# Schematic.net
KiCad netlist of a schematic drawn in Altium Designer
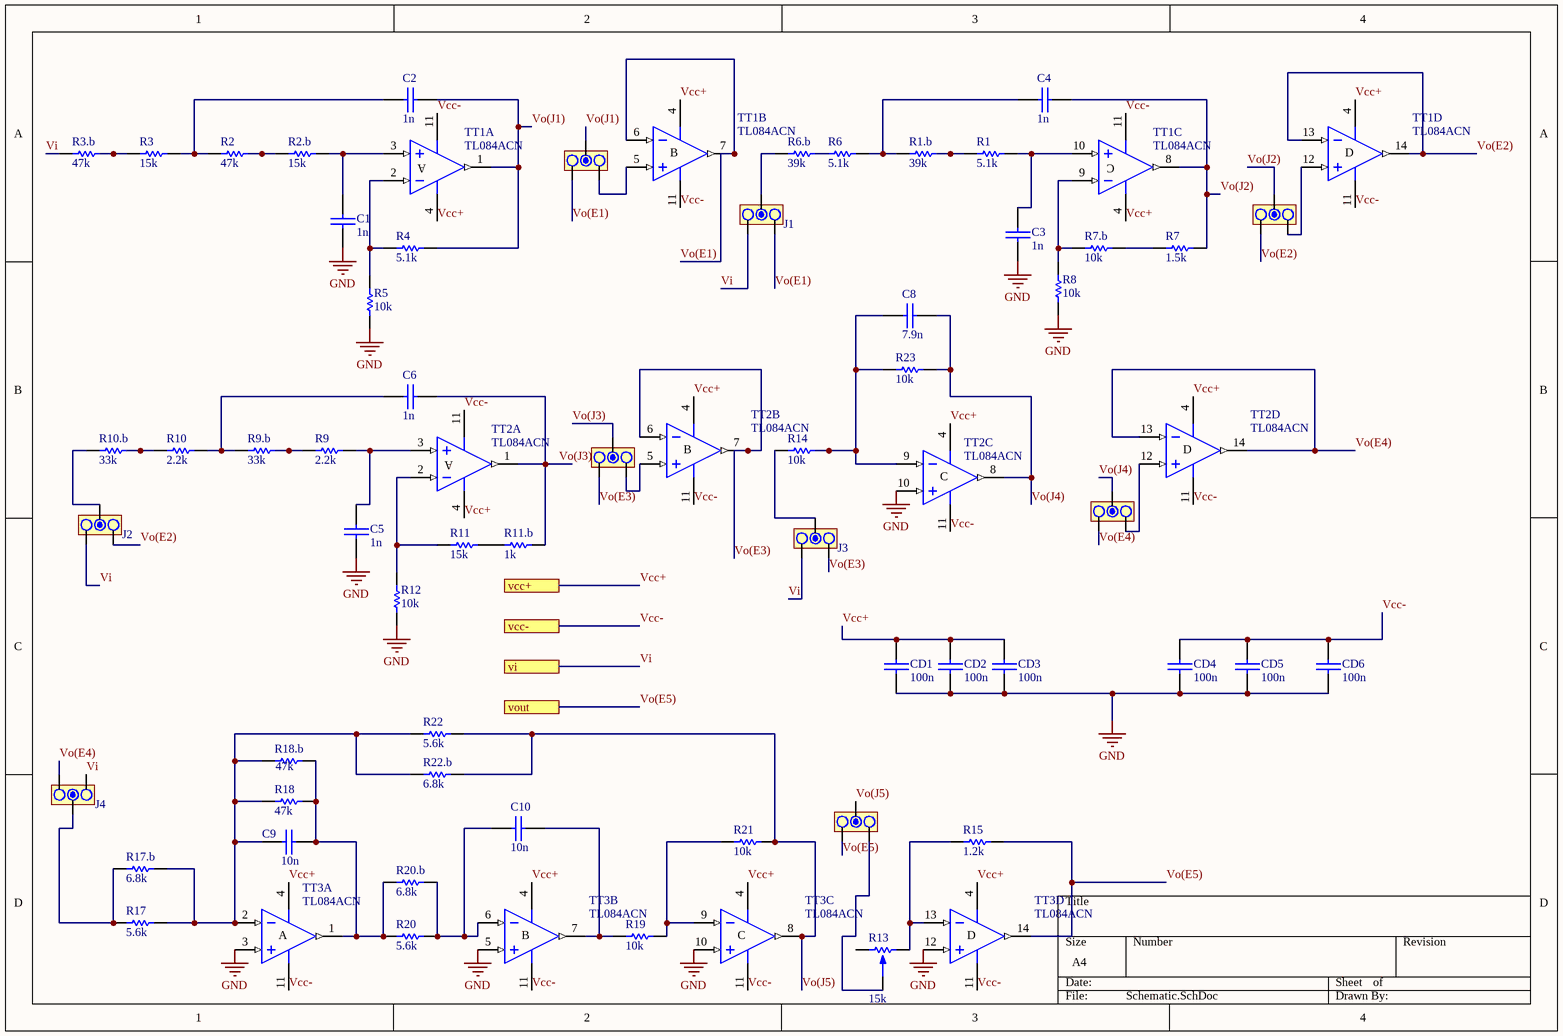
[diagram p0: Schematic.SchDoc]

(export (version "E")
  (design (tool "Eeschema 10.0.6"))
  (components
    (comp (ref "C1") (value "1n") (footprint "CAP200") (libsource (lib "LIBEBAL") (part "CAP")))
    (comp (ref "C2") (value "1n") (footprint "CAP200") (libsource (lib "LIBEBAL") (part "CAP")))
    (comp (ref "C3") (value "1n") (footprint "CAP200") (libsource (lib "LIBEBAL") (part "CAP")))
    (comp (ref "C4") (value "1n") (footprint "CAP200") (libsource (lib "LIBEBAL") (part "CAP")))
    (comp (ref "C5") (value "1n") (footprint "CAP200") (libsource (lib "LIBEBAL") (part "CAP")))
    (comp (ref "C6") (value "1n") (footprint "CAP200") (libsource (lib "LIBEBAL") (part "CAP")))
    (comp (ref "C8") (value "7.9n") (footprint "CAP200") (libsource (lib "LIBEBAL") (part "CAP")))
    (comp (ref "C9") (value "10n") (footprint "CAP200") (libsource (lib "LIBEBAL") (part "CAP")))
    (comp (ref "C10") (value "10n") (footprint "CAP200") (libsource (lib "LIBEBAL") (part "CAP")))
    (comp (ref "CD1") (value "100n") (footprint "CAP200") (libsource (lib "LIBEBAL") (part "CAP")))
    (comp (ref "CD2") (value "100n") (footprint "CAP200") (libsource (lib "LIBEBAL") (part "CAP")))
    (comp (ref "CD3") (value "100n") (footprint "CAP200") (libsource (lib "LIBEBAL") (part "CAP")))
    (comp (ref "CD4") (value "100n") (footprint "CAP200") (libsource (lib "LIBEBAL") (part "CAP")))
    (comp (ref "CD5") (value "100n") (footprint "CAP200") (libsource (lib "LIBEBAL") (part "CAP")))
    (comp (ref "CD6") (value "100n") (footprint "CAP200") (libsource (lib "LIBEBAL") (part "CAP")))
    (comp (ref "J1") (value "JUMPER") (footprint "JUMPER3") (libsource (lib "LIBEBAL") (part "JUMPER3")))
    (comp (ref "J2") (value "JUMPER") (footprint "JUMPER3") (libsource (lib "LIBEBAL") (part "JUMPER3")))
    (comp (ref "J3") (value "JUMPER") (footprint "JUMPER3") (libsource (lib "LIBEBAL") (part "JUMPER3")))
    (comp (ref "J4") (value "JUMPER") (footprint "JUMPER3") (libsource (lib "") (part "JUMPER3_1")))
    (comp (ref "Jumper1") (value "JUMPER") (footprint "JUMPER3") (libsource (lib "LIBEBAL") (part "JUMPER3")))
    (comp (ref "Jumper2") (value "JUMPER") (footprint "JUMPER3") (libsource (lib "LIBEBAL") (part "JUMPER3")))
    (comp (ref "Jumper3") (value "JUMPER") (footprint "JUMPER3") (libsource (lib "LIBEBAL") (part "JUMPER3")))
    (comp (ref "Jumper4") (value "JUMPER") (footprint "JUMPER3") (libsource (lib "LIBEBAL") (part "JUMPER3")))
    (comp (ref "Jumper5") (value "JUMPER") (footprint "JUMPER3") (libsource (lib "LIBEBAL") (part "JUMPER3")))
    (comp (ref "R1") (value "5.1k") (footprint "RES400") (libsource (lib "LIBEBAL") (part "RES")))
    (comp (ref "R1.b") (value "39k") (footprint "RES400") (libsource (lib "LIBEBAL") (part "RES")))
    (comp (ref "R2") (value "47k") (footprint "RES400") (libsource (lib "LIBEBAL") (part "RES")))
    (comp (ref "R2.b") (value "15k") (footprint "RES400") (libsource (lib "LIBEBAL") (part "RES")))
    (comp (ref "R3") (value "15k") (footprint "RES400") (libsource (lib "LIBEBAL") (part "RES")))
    (comp (ref "R3.b") (value "47k") (footprint "RES400") (libsource (lib "LIBEBAL") (part "RES")))
    (comp (ref "R4") (value "5.1k") (footprint "RES400") (libsource (lib "LIBEBAL") (part "RES")))
    (comp (ref "R5") (value "10k") (footprint "RES400") (libsource (lib "LIBEBAL") (part "RES")))
    (comp (ref "R6") (value "5.1k") (footprint "RES400") (libsource (lib "LIBEBAL") (part "RES")))
    (comp (ref "R6.b") (value "39k") (footprint "RES400") (libsource (lib "LIBEBAL") (part "RES")))
    (comp (ref "R7") (value "1.5k") (footprint "RES400") (libsource (lib "LIBEBAL") (part "RES")))
    (comp (ref "R7.b") (value "10k") (footprint "RES400") (libsource (lib "LIBEBAL") (part "RES")))
    (comp (ref "R8") (value "10k") (footprint "RES400") (libsource (lib "LIBEBAL") (part "RES")))
    (comp (ref "R9") (value "2.2k") (footprint "RES400") (libsource (lib "LIBEBAL") (part "RES")))
    (comp (ref "R9.b") (value "33k") (footprint "RES400") (libsource (lib "LIBEBAL") (part "RES")))
    (comp (ref "R10") (value "2.2k") (footprint "RES400") (libsource (lib "LIBEBAL") (part "RES")))
    (comp (ref "R10.b") (value "33k") (footprint "RES400") (libsource (lib "LIBEBAL") (part "RES")))
    (comp (ref "R11") (value "15k") (footprint "RES400") (libsource (lib "LIBEBAL") (part "RES")))
    (comp (ref "R11.b") (value "1k") (footprint "RES400") (libsource (lib "LIBEBAL") (part "RES")))
    (comp (ref "R12") (value "10k") (footprint "RES400") (libsource (lib "LIBEBAL") (part "RES")))
    (comp (ref "R13") (value "15k") (footprint "PRESET V") (libsource (lib "LIBEBAL") (part "PRESET")))
    (comp (ref "R14") (value "10k") (footprint "RES400") (libsource (lib "LIBEBAL") (part "RES")))
    (comp (ref "R15") (value "1.2k") (footprint "RES400") (libsource (lib "LIBEBAL") (part "RES")))
    (comp (ref "R17") (value "5.6k") (footprint "RES400") (libsource (lib "LIBEBAL") (part "RES")))
    (comp (ref "R17.b") (value "6.8k") (footprint "RES400") (libsource (lib "LIBEBAL") (part "RES")))
    (comp (ref "R18") (value "47k") (footprint "RES400") (libsource (lib "LIBEBAL") (part "RES")))
    (comp (ref "R18.b") (value "47k") (footprint "RES400") (libsource (lib "LIBEBAL") (part "RES")))
    (comp (ref "R19") (value "10k") (footprint "RES400") (libsource (lib "LIBEBAL") (part "RES")))
    (comp (ref "R20") (value "5.6k") (footprint "RES400") (libsource (lib "LIBEBAL") (part "RES")))
    (comp (ref "R20.b") (value "6.8k") (footprint "RES400") (libsource (lib "LIBEBAL") (part "RES")))
    (comp (ref "R21") (value "10k") (footprint "RES400") (libsource (lib "LIBEBAL") (part "RES")))
    (comp (ref "R22") (value "5.6k") (footprint "RES400") (libsource (lib "LIBEBAL") (part "RES")))
    (comp (ref "R22.b") (value "6.8k") (footprint "RES400") (libsource (lib "LIBEBAL") (part "RES")))
    (comp (ref "R23") (value "10k") (footprint "RES400") (libsource (lib "LIBEBAL") (part "RES")))
    (comp (ref "TT1")
      (value "TL084ACN")
      (footprint "DIP14")
      (description "General-Purpose J-FET Quad Operational Amplifier")
      (fields (field (name "PUBLISHER") "Altium Limited"))
      (libsource (lib "ST Operational Amplifier") (part "TL084ACN"))
    )
    (comp (ref "TT2")
      (value "TL084ACN")
      (footprint "DIP14")
      (description "General-Purpose J-FET Quad Operational Amplifier")
      (fields (field (name "PUBLISHER") "Altium Limited"))
      (libsource (lib "ST Operational Amplifier") (part "TL084ACN"))
    )
    (comp (ref "TT3")
      (value "TL084ACN")
      (footprint "DIP14")
      (description "General-Purpose J-FET Quad Operational Amplifier")
      (fields (field (name "PUBLISHER") "Altium Limited"))
      (libsource (lib "ST Operational Amplifier") (part "TL084ACN"))
    )
  )
  (nets
    (net (code "1") (name "/Vcc+") (class "Default")
      (node (ref "CD1") (pin "1") (pinfunction "1_1") (pintype "passive"))
      (node (ref "CD2") (pin "1") (pinfunction "1_1") (pintype "passive"))
      (node (ref "CD3") (pin "1") (pinfunction "1_1") (pintype "passive"))
      (node (ref "TT1") (pin "4") (pinfunction "V+_4") (pintype "power_in"))
      (node (ref "TT2") (pin "4") (pinfunction "V+_4") (pintype "power_in"))
      (node (ref "TT3") (pin "4") (pinfunction "V+_4") (pintype "power_in"))
    )
    (net (code "2") (name "/Vcc-") (class "Default")
      (node (ref "CD4") (pin "1") (pinfunction "1_1") (pintype "passive"))
      (node (ref "CD5") (pin "1") (pinfunction "1_1") (pintype "passive"))
      (node (ref "CD6") (pin "1") (pinfunction "1_1") (pintype "passive"))
      (node (ref "TT1") (pin "11") (pinfunction "V-_11") (pintype "power_in"))
      (node (ref "TT2") (pin "11") (pinfunction "V-_11") (pintype "power_in"))
      (node (ref "TT3") (pin "11") (pinfunction "V-_11") (pintype "power_in"))
    )
    (net (code "3") (name "/Vi") (class "Default")
      (node (ref "J1") (pin "3") (pinfunction "3_3") (pintype "passive"))
      (node (ref "J2") (pin "3") (pinfunction "3_3") (pintype "passive"))
      (node (ref "J3") (pin "3") (pinfunction "3_3") (pintype "passive"))
      (node (ref "J4") (pin "3") (pinfunction "3_3") (pintype "passive"))
      (node (ref "R3.b") (pin "1") (pinfunction "1_1") (pintype "passive"))
    )
    (net (code "4") (name "/Vo(E1)") (class "Default")
      (node (ref "J1") (pin "1") (pinfunction "1_1") (pintype "passive"))
      (node (ref "Jumper1") (pin "3") (pinfunction "3_3") (pintype "passive"))
      (node (ref "TT1") (pin "6") (pinfunction "IN-_6") (pintype "input"))
      (node (ref "TT1") (pin "7") (pinfunction "OUT_7") (pintype "output"))
    )
    (net (code "5") (name "/Vo(E2)") (class "Default")
      (node (ref "J2") (pin "1") (pinfunction "1_1") (pintype "passive"))
      (node (ref "Jumper2") (pin "3") (pinfunction "3_3") (pintype "passive"))
      (node (ref "TT1") (pin "13") (pinfunction "IN-_13") (pintype "input"))
      (node (ref "TT1") (pin "14") (pinfunction "OUT_14") (pintype "output"))
    )
    (net (code "6") (name "/Vo(E3)") (class "Default")
      (node (ref "J3") (pin "1") (pinfunction "1_1") (pintype "passive"))
      (node (ref "Jumper3") (pin "3") (pinfunction "3_3") (pintype "passive"))
      (node (ref "TT2") (pin "6") (pinfunction "IN-_6") (pintype "input"))
      (node (ref "TT2") (pin "7") (pinfunction "OUT_7") (pintype "output"))
    )
    (net (code "7") (name "/Vo(E4)") (class "Default")
      (node (ref "J4") (pin "1") (pinfunction "1_1") (pintype "passive"))
      (node (ref "Jumper4") (pin "3") (pinfunction "3_3") (pintype "passive"))
      (node (ref "TT2") (pin "13") (pinfunction "IN-_13") (pintype "input"))
      (node (ref "TT2") (pin "14") (pinfunction "OUT_14") (pintype "output"))
    )
    (net (code "8") (name "/Vo(E5)") (class "Default")
      (node (ref "Jumper5") (pin "3") (pinfunction "3_3") (pintype "passive"))
      (node (ref "R15") (pin "2") (pinfunction "2_2") (pintype "passive"))
      (node (ref "TT3") (pin "14") (pinfunction "OUT_14") (pintype "output"))
    )
    (net (code "9") (name "/Vo(J1)") (class "Default")
      (node (ref "C2") (pin "2") (pinfunction "2_2") (pintype "passive"))
      (node (ref "Jumper1") (pin "2") (pinfunction "2_2") (pintype "passive"))
      (node (ref "R4") (pin "1") (pinfunction "1_1") (pintype "passive"))
      (node (ref "TT1") (pin "1") (pinfunction "OUT_1") (pintype "output"))
    )
    (net (code "10") (name "/Vo(J2)") (class "Default")
      (node (ref "C4") (pin "2") (pinfunction "2_2") (pintype "passive"))
      (node (ref "Jumper2") (pin "2") (pinfunction "2_2") (pintype "passive"))
      (node (ref "R7") (pin "2") (pinfunction "2_2") (pintype "passive"))
      (node (ref "TT1") (pin "8") (pinfunction "OUT_8") (pintype "output"))
    )
    (net (code "11") (name "/Vo(J3)") (class "Default")
      (node (ref "C6") (pin "2") (pinfunction "2_2") (pintype "passive"))
      (node (ref "Jumper3") (pin "2") (pinfunction "2_2") (pintype "passive"))
      (node (ref "R11.b") (pin "1") (pinfunction "1_1") (pintype "passive"))
      (node (ref "TT2") (pin "1") (pinfunction "OUT_1") (pintype "output"))
    )
    (net (code "12") (name "/Vo(J4)") (class "Default")
      (node (ref "C8") (pin "2") (pinfunction "2_2") (pintype "passive"))
      (node (ref "Jumper4") (pin "2") (pinfunction "2_2") (pintype "passive"))
      (node (ref "R23") (pin "2") (pinfunction "2_2") (pintype "passive"))
      (node (ref "TT2") (pin "8") (pinfunction "OUT_8") (pintype "output"))
    )
    (net (code "13") (name "/Vo(J5)") (class "Default")
      (node (ref "Jumper5") (pin "2") (pinfunction "2_2") (pintype "passive"))
      (node (ref "R21") (pin "2") (pinfunction "2_2") (pintype "passive"))
      (node (ref "R22") (pin "2") (pinfunction "2_2") (pintype "passive"))
      (node (ref "R22.b") (pin "2") (pinfunction "2_2") (pintype "passive"))
      (node (ref "TT3") (pin "8") (pinfunction "OUT_8") (pintype "output"))
    )
    (net (code "14") (name "GND") (class "Default")
      (node (ref "C1") (pin "1") (pinfunction "1_1") (pintype "passive"))
      (node (ref "C3") (pin "1") (pinfunction "1_1") (pintype "passive"))
      (node (ref "C5") (pin "1") (pinfunction "1_1") (pintype "passive"))
      (node (ref "CD1") (pin "2") (pinfunction "2_2") (pintype "passive"))
      (node (ref "CD2") (pin "2") (pinfunction "2_2") (pintype "passive"))
      (node (ref "CD3") (pin "2") (pinfunction "2_2") (pintype "passive"))
      (node (ref "CD4") (pin "2") (pinfunction "2_2") (pintype "passive"))
      (node (ref "CD5") (pin "2") (pinfunction "2_2") (pintype "passive"))
      (node (ref "CD6") (pin "2") (pinfunction "2_2") (pintype "passive"))
      (node (ref "R12") (pin "1") (pinfunction "1_1") (pintype "passive"))
      (node (ref "R5") (pin "1") (pinfunction "1_1") (pintype "passive"))
      (node (ref "R8") (pin "1") (pinfunction "1_1") (pintype "passive"))
      (node (ref "TT2") (pin "10") (pinfunction "IN+_10") (pintype "input"))
      (node (ref "TT3") (pin "10") (pinfunction "IN+_10") (pintype "input"))
      (node (ref "TT3") (pin "12") (pinfunction "IN+_12") (pintype "input"))
      (node (ref "TT3") (pin "3") (pinfunction "IN+_3") (pintype "input"))
      (node (ref "TT3") (pin "5") (pinfunction "IN+_5") (pintype "input"))
    )
    (net (code "15") (name "Net-(C2-Pad1)") (class "Default")
      (node (ref "C2") (pin "1") (pinfunction "1_1") (pintype "passive"))
      (node (ref "R2") (pin "1") (pinfunction "1_1") (pintype "passive"))
      (node (ref "R3") (pin "2") (pinfunction "2_2") (pintype "passive"))
    )
    (net (code "16") (name "Net-(C4-Pad1)") (class "Default")
      (node (ref "C4") (pin "1") (pinfunction "1_1") (pintype "passive"))
      (node (ref "R1.b") (pin "1") (pinfunction "1_1") (pintype "passive"))
      (node (ref "R6") (pin "2") (pinfunction "2_2") (pintype "passive"))
    )
    (net (code "17") (name "Net-(C6-Pad1)") (class "Default")
      (node (ref "C6") (pin "1") (pinfunction "1_1") (pintype "passive"))
      (node (ref "R10") (pin "2") (pinfunction "2_2") (pintype "passive"))
      (node (ref "R9.b") (pin "1") (pinfunction "1_1") (pintype "passive"))
    )
    (net (code "18") (name "Net-(J1-Pad2)") (class "Default")
      (node (ref "J1") (pin "2") (pinfunction "2_2") (pintype "passive"))
      (node (ref "R6.b") (pin "1") (pinfunction "1_1") (pintype "passive"))
    )
    (net (code "19") (name "Net-(J2-Pad2)") (class "Default")
      (node (ref "J2") (pin "2") (pinfunction "2_2") (pintype "passive"))
      (node (ref "R10.b") (pin "1") (pinfunction "1_1") (pintype "passive"))
    )
    (net (code "20") (name "Net-(J3-Pad2)") (class "Default")
      (node (ref "J3") (pin "2") (pinfunction "2_2") (pintype "passive"))
      (node (ref "R14") (pin "1") (pinfunction "1_1") (pintype "passive"))
    )
    (net (code "21") (name "Net-(J4-Pad2)") (class "Default")
      (node (ref "J4") (pin "2") (pinfunction "2_2") (pintype "passive"))
      (node (ref "R17") (pin "1") (pinfunction "1_1") (pintype "passive"))
      (node (ref "R17.b") (pin "1") (pinfunction "1_1") (pintype "passive"))
    )
    (net (code "22") (name "Net-(Jumper5-Pad1)") (class "Default")
      (node (ref "Jumper5") (pin "1") (pinfunction "1_1") (pintype "passive"))
      (node (ref "R13") (pin "2") (pinfunction "2_2") (pintype "passive"))
    )
    (net (code "23") (name "Net-(R1-Pad1)") (class "Default")
      (node (ref "R1") (pin "1") (pinfunction "1_1") (pintype "passive"))
      (node (ref "R1.b") (pin "2") (pinfunction "2_2") (pintype "passive"))
    )
    (net (code "24") (name "Net-(R2-Pad2)") (class "Default")
      (node (ref "R2") (pin "2") (pinfunction "2_2") (pintype "passive"))
      (node (ref "R2.b") (pin "1") (pinfunction "1_1") (pintype "passive"))
    )
    (net (code "25") (name "Net-(R3-Pad1)") (class "Default")
      (node (ref "R3") (pin "1") (pinfunction "1_1") (pintype "passive"))
      (node (ref "R3.b") (pin "2") (pinfunction "2_2") (pintype "passive"))
    )
    (net (code "26") (name "Net-(R6-Pad1)") (class "Default")
      (node (ref "R6") (pin "1") (pinfunction "1_1") (pintype "passive"))
      (node (ref "R6.b") (pin "2") (pinfunction "2_2") (pintype "passive"))
    )
    (net (code "27") (name "Net-(R7-Pad1)") (class "Default")
      (node (ref "R7") (pin "1") (pinfunction "1_1") (pintype "passive"))
      (node (ref "R7.b") (pin "1") (pinfunction "1_1") (pintype "passive"))
    )
    (net (code "28") (name "Net-(R9-Pad1)") (class "Default")
      (node (ref "R9") (pin "1") (pinfunction "1_1") (pintype "passive"))
      (node (ref "R9.b") (pin "2") (pinfunction "2_2") (pintype "passive"))
    )
    (net (code "29") (name "Net-(R10-Pad1)") (class "Default")
      (node (ref "R10") (pin "1") (pinfunction "1_1") (pintype "passive"))
      (node (ref "R10.b") (pin "2") (pinfunction "2_2") (pintype "passive"))
    )
    (net (code "30") (name "Net-(R11-Pad1)") (class "Default")
      (node (ref "R11") (pin "1") (pinfunction "1_1") (pintype "passive"))
      (node (ref "R11.b") (pin "2") (pinfunction "2_2") (pintype "passive"))
    )
    (net (code "31") (name "Net-(TT1A-IN+)") (class "Default")
      (node (ref "C1") (pin "2") (pinfunction "2_2") (pintype "passive"))
      (node (ref "R2.b") (pin "2") (pinfunction "2_2") (pintype "passive"))
      (node (ref "TT1") (pin "3") (pinfunction "IN+_3") (pintype "input"))
    )
    (net (code "32") (name "Net-(TT1A-IN-)") (class "Default")
      (node (ref "R4") (pin "2") (pinfunction "2_2") (pintype "passive"))
      (node (ref "R5") (pin "2") (pinfunction "2_2") (pintype "passive"))
      (node (ref "TT1") (pin "2") (pinfunction "IN-_2") (pintype "input"))
    )
    (net (code "33") (name "Net-(TT1B-IN+)") (class "Default")
      (node (ref "Jumper1") (pin "1") (pinfunction "1_1") (pintype "passive"))
      (node (ref "TT1") (pin "5") (pinfunction "IN+_5") (pintype "input"))
    )
    (net (code "34") (name "Net-(TT1C-IN+)") (class "Default")
      (node (ref "C3") (pin "2") (pinfunction "2_2") (pintype "passive"))
      (node (ref "R1") (pin "2") (pinfunction "2_2") (pintype "passive"))
      (node (ref "TT1") (pin "10") (pinfunction "IN+_10") (pintype "input"))
    )
    (net (code "35") (name "Net-(TT1C-IN-)") (class "Default")
      (node (ref "R7.b") (pin "2") (pinfunction "2_2") (pintype "passive"))
      (node (ref "R8") (pin "2") (pinfunction "2_2") (pintype "passive"))
      (node (ref "TT1") (pin "9") (pinfunction "IN-_9") (pintype "input"))
    )
    (net (code "36") (name "Net-(TT1D-IN+)") (class "Default")
      (node (ref "Jumper2") (pin "1") (pinfunction "1_1") (pintype "passive"))
      (node (ref "TT1") (pin "12") (pinfunction "IN+_12") (pintype "input"))
    )
    (net (code "37") (name "Net-(TT2A-IN+)") (class "Default")
      (node (ref "C5") (pin "2") (pinfunction "2_2") (pintype "passive"))
      (node (ref "R9") (pin "2") (pinfunction "2_2") (pintype "passive"))
      (node (ref "TT2") (pin "3") (pinfunction "IN+_3") (pintype "input"))
    )
    (net (code "38") (name "Net-(TT2A-IN-)") (class "Default")
      (node (ref "R11") (pin "2") (pinfunction "2_2") (pintype "passive"))
      (node (ref "R12") (pin "2") (pinfunction "2_2") (pintype "passive"))
      (node (ref "TT2") (pin "2") (pinfunction "IN-_2") (pintype "input"))
    )
    (net (code "39") (name "Net-(TT2B-IN+)") (class "Default")
      (node (ref "Jumper3") (pin "1") (pinfunction "1_1") (pintype "passive"))
      (node (ref "TT2") (pin "5") (pinfunction "IN+_5") (pintype "input"))
    )
    (net (code "40") (name "Net-(TT2C-IN-)") (class "Default")
      (node (ref "C8") (pin "1") (pinfunction "1_1") (pintype "passive"))
      (node (ref "R14") (pin "2") (pinfunction "2_2") (pintype "passive"))
      (node (ref "R23") (pin "1") (pinfunction "1_1") (pintype "passive"))
      (node (ref "TT2") (pin "9") (pinfunction "IN-_9") (pintype "input"))
    )
    (net (code "41") (name "Net-(TT2D-IN+)") (class "Default")
      (node (ref "Jumper4") (pin "1") (pinfunction "1_1") (pintype "passive"))
      (node (ref "TT2") (pin "12") (pinfunction "IN+_12") (pintype "input"))
    )
    (net (code "42") (name "Net-(TT3A-IN-)") (class "Default")
      (node (ref "C9") (pin "1") (pinfunction "1_1") (pintype "passive"))
      (node (ref "R17") (pin "2") (pinfunction "2_2") (pintype "passive"))
      (node (ref "R17.b") (pin "2") (pinfunction "2_2") (pintype "passive"))
      (node (ref "R18") (pin "1") (pinfunction "1_1") (pintype "passive"))
      (node (ref "R18.b") (pin "1") (pinfunction "1_1") (pintype "passive"))
      (node (ref "R22") (pin "1") (pinfunction "1_1") (pintype "passive"))
      (node (ref "R22.b") (pin "1") (pinfunction "1_1") (pintype "passive"))
      (node (ref "TT3") (pin "2") (pinfunction "IN-_2") (pintype "input"))
    )
    (net (code "43") (name "Net-(TT3A-OUT)") (class "Default")
      (node (ref "C9") (pin "2") (pinfunction "2_2") (pintype "passive"))
      (node (ref "R18") (pin "2") (pinfunction "2_2") (pintype "passive"))
      (node (ref "R18.b") (pin "2") (pinfunction "2_2") (pintype "passive"))
      (node (ref "R20") (pin "1") (pinfunction "1_1") (pintype "passive"))
      (node (ref "R20.b") (pin "1") (pinfunction "1_1") (pintype "passive"))
      (node (ref "TT3") (pin "1") (pinfunction "OUT_1") (pintype "output"))
    )
    (net (code "44") (name "Net-(TT3B-IN-)") (class "Default")
      (node (ref "C10") (pin "1") (pinfunction "1_1") (pintype "passive"))
      (node (ref "R20") (pin "2") (pinfunction "2_2") (pintype "passive"))
      (node (ref "R20.b") (pin "2") (pinfunction "2_2") (pintype "passive"))
      (node (ref "TT3") (pin "6") (pinfunction "IN-_6") (pintype "input"))
    )
    (net (code "45") (name "Net-(TT3B-OUT)") (class "Default")
      (node (ref "C10") (pin "2") (pinfunction "2_2") (pintype "passive"))
      (node (ref "R19") (pin "1") (pinfunction "1_1") (pintype "passive"))
      (node (ref "TT3") (pin "7") (pinfunction "OUT_7") (pintype "output"))
    )
    (net (code "46") (name "Net-(TT3C-IN-)") (class "Default")
      (node (ref "R19") (pin "2") (pinfunction "2_2") (pintype "passive"))
      (node (ref "R21") (pin "1") (pinfunction "1_1") (pintype "passive"))
      (node (ref "TT3") (pin "9") (pinfunction "IN-_9") (pintype "input"))
    )
    (net (code "47") (name "Net-(TT3D-IN-)") (class "Default")
      (node (ref "R13") (pin "1") (pinfunction "1_1") (pintype "passive"))
      (node (ref "R15") (pin "1") (pinfunction "1_1") (pintype "passive"))
      (node (ref "TT3") (pin "13") (pinfunction "IN-_13") (pintype "input"))
    )
    (net (code "48") (name "unconnected-(R13-Pad3)") (class "Default")
      (node (ref "R13") (pin "3") (pinfunction "3_3") (pintype "passive"))
    )
  )
)
